# interior_panel.net
KiCad netlist of a schematic drawn in EAGLE
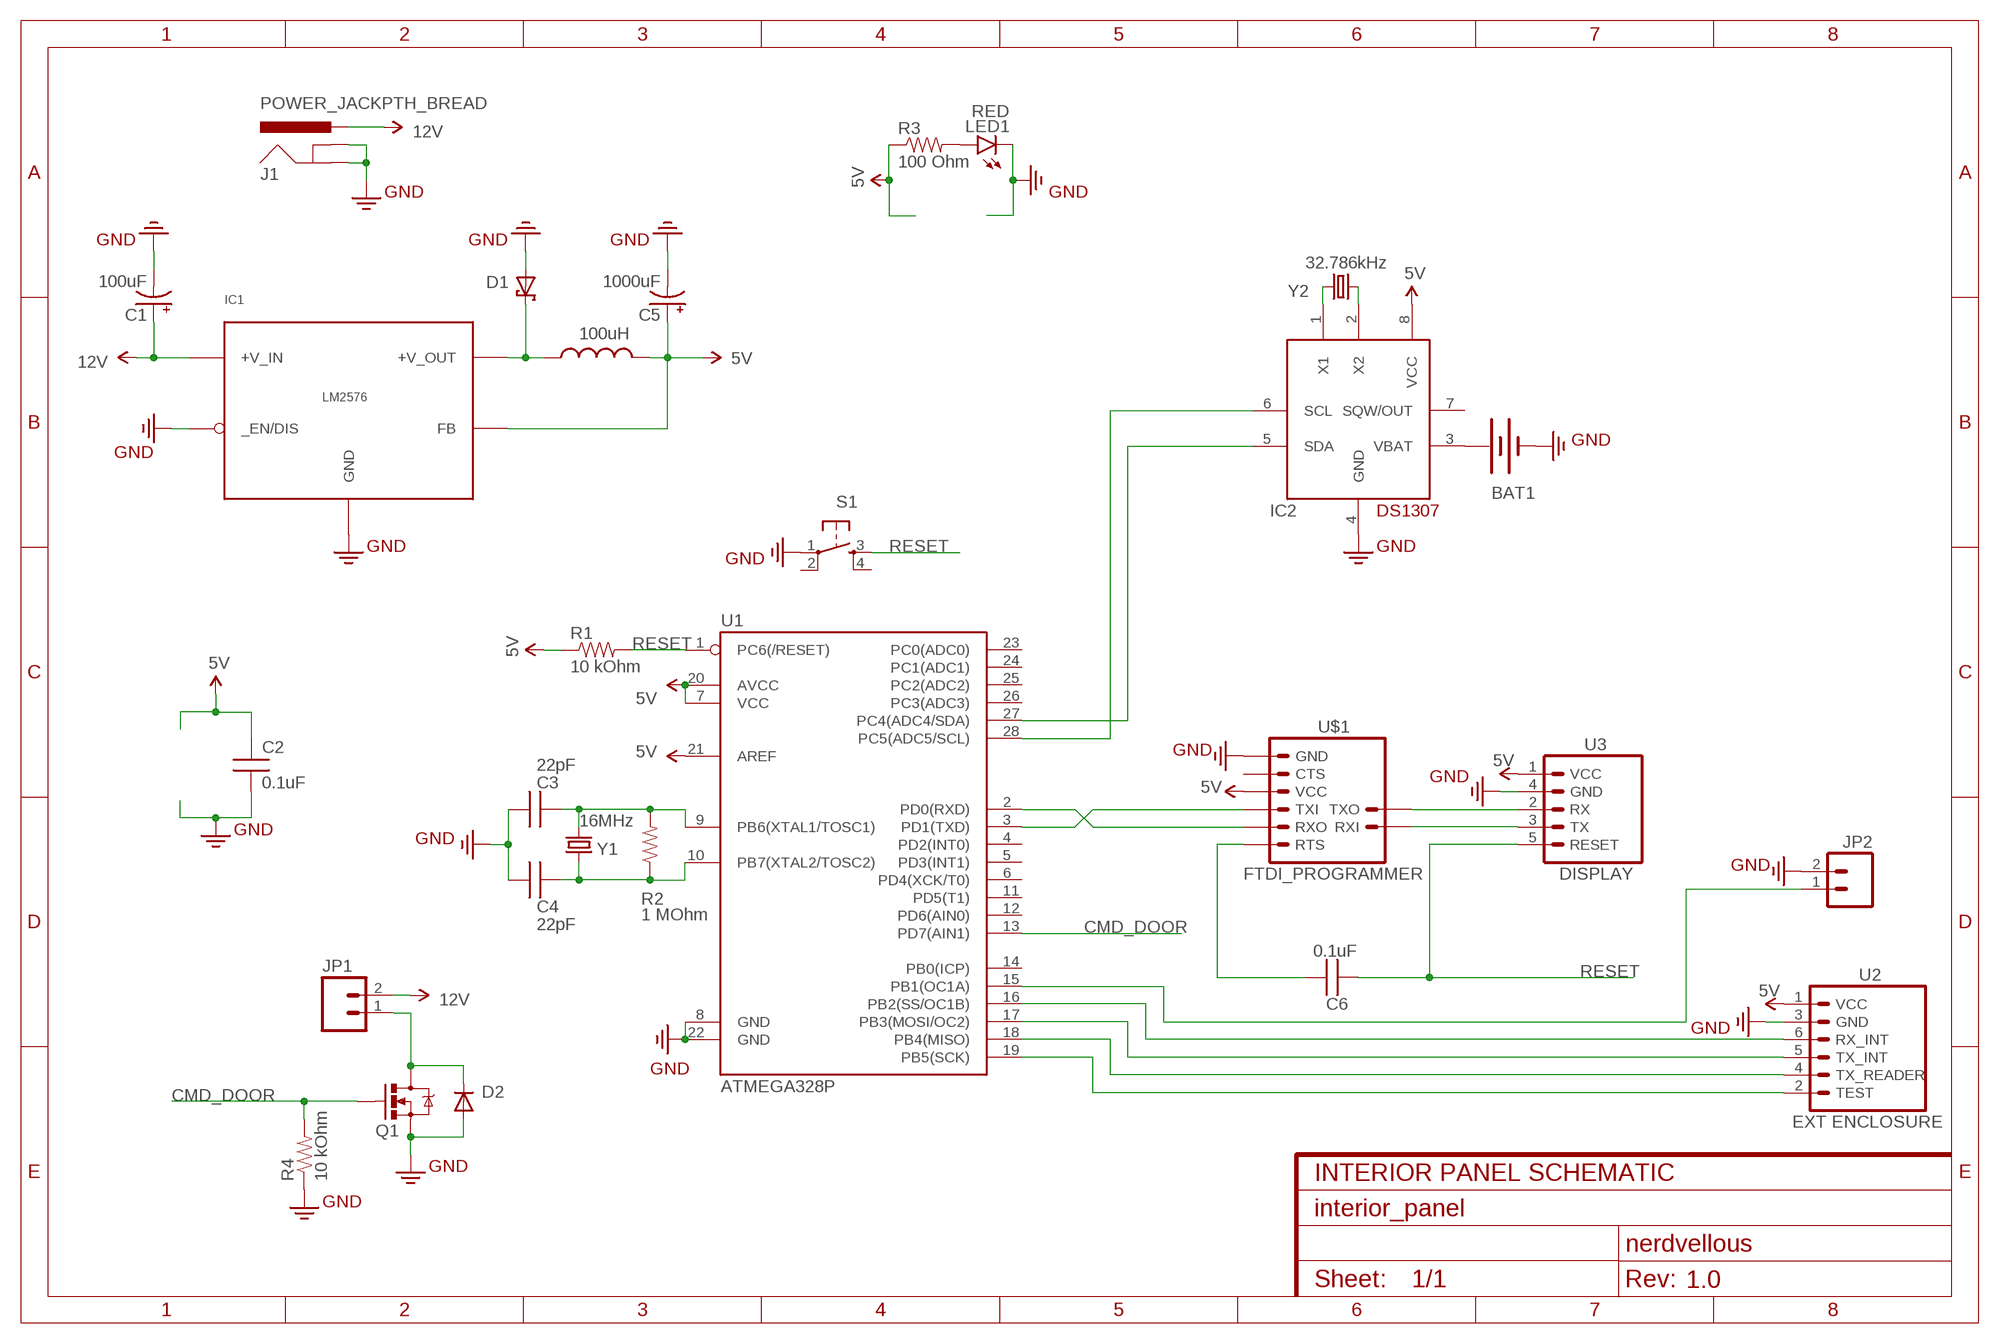
[diagram p0: schematic, sheet 1]

(export (version "E")
  (design (tool "Eeschema 10.0.6"))
  (components
    (comp (ref "BAT1")
      (value "BATTERY12MMFULLPTH")
      (footprint "eagle-import:BATTCON_12MM_FULLPTH")
      (libsource (lib "eagle-import") (part "BATTERY12MMFULLPTH"))
    )
    (comp (ref "C1")
      (value "100uF")
      (footprint "eagle-import:CPOL-RADIAL-100UF-25V")
      (libsource (lib "eagle-import") (part "CAP-100UF"))
    )
    (comp (ref "C2")
      (value "0.1uF")
      (footprint "eagle-import:CAP-PTH-SMALL")
      (libsource (lib "eagle-import") (part "CAP-0.1UF"))
    )
    (comp (ref "C3")
      (value "22pF")
      (footprint "eagle-import:CAP-PTH-SMALL")
      (libsource (lib "eagle-import") (part "CAP-22PF"))
    )
    (comp (ref "C4")
      (value "22pF")
      (footprint "eagle-import:CAP-PTH-SMALL")
      (libsource (lib "eagle-import") (part "CAP-22PF"))
    )
    (comp (ref "C5")
      (value "1000uF")
      (footprint "eagle-import:CPOL-RADIAL-100UF-25V")
      (libsource (lib "eagle-import") (part "CAP-1000UF16V"))
    )
    (comp (ref "C6")
      (value "0.1uF")
      (footprint "eagle-import:CAP-PTH-SMALL")
      (libsource (lib "eagle-import") (part "CAP-0.1UF"))
    )
    (comp (ref "D1")
      (value "1N5822")
      (footprint "eagle-import:DO-201AD")
      (libsource (lib "eagle-import") (part "1N5822"))
    )
    (comp (ref "D2")
      (value "1N4004")
      (footprint "eagle-import:DO-41")
      (libsource (lib "eagle-import") (part "1N4004"))
    )
    (comp (ref "IC1")
      (value "LM2576")
      (footprint "eagle-import:TO-220-5PIN")
      (libsource (lib "eagle-import") (part "LM2576"))
    )
    (comp (ref "IC2")
      (value "DS1307")
      (footprint "eagle-import:DIL08")
      (libsource (lib "eagle-import") (part "DS1307"))
    )
    (comp (ref "J1")
      (value "POWER_JACKPTH_BREAD")
      (footprint "eagle-import:POWER_JACK_PTH_BREAD")
      (libsource (lib "eagle-import") (part "POWER_JACKPTH_BREAD"))
    )
    (comp (ref "JP1")
      (value "M02PTH")
      (footprint "eagle-import:1X02")
      (libsource (lib "eagle-import") (part "M02PTH"))
    )
    (comp (ref "JP2")
      (value "M02PTH")
      (footprint "eagle-import:1X02")
      (libsource (lib "eagle-import") (part "M02PTH"))
    )
    (comp (ref "L1")
      (value "100uH")
      (footprint "eagle-import:RLB0912")
      (libsource (lib "eagle-import") (part "INDUCTORRLB0912"))
    )
    (comp (ref "LED1")
      (value "RED")
      (footprint "eagle-import:LED5MM")
      (libsource (lib "eagle-import") (part "LED5MM"))
    )
    (comp (ref "Q1")
      (value "MOSFET-NCHANNELFQP30N06L")
      (footprint "eagle-import:TO220V")
      (libsource (lib "eagle-import") (part "MOSFET-NCHANNELFQP30N06L"))
    )
    (comp (ref "R1")
      (value "10 kOhm")
      (footprint "eagle-import:AXIAL-0.3")
      (libsource (lib "eagle-import") (part "RES-10KOHM"))
    )
    (comp (ref "R2")
      (value "1 MOhm")
      (footprint "eagle-import:AXIAL-0.3")
      (libsource (lib "eagle-import") (part "RES-1MOHM"))
    )
    (comp (ref "R3")
      (value "100 Ohm")
      (footprint "eagle-import:AXIAL-0.3")
      (libsource (lib "eagle-import") (part "RES-100OHM"))
    )
    (comp (ref "R4")
      (value "10 kOhm")
      (footprint "eagle-import:AXIAL-0.3")
      (libsource (lib "eagle-import") (part "RES-10KOHM"))
    )
    (comp (ref "S1")
      (value "TAC_SWITCHPTH")
      (footprint "eagle-import:TACTILE-PTH")
      (libsource (lib "eagle-import") (part "TAC_SWITCHPTH"))
    )
    (comp (ref "U$1")
      (value "FTDI_PROGRAMMER")
      (footprint "eagle-import:FTDI_CABLE_JUMPER")
      (libsource (lib "eagle-import") (part "FTDI_PROGRAMMER"))
    )
    (comp (ref "U1")
      (value "ATMEGA328P")
      (footprint "eagle-import:DIL28")
      (libsource (lib "eagle-import") (part "ATMEGA328P"))
    )
    (comp (ref "U2")
      (value "EXT ENCLOSURE")
      (footprint "eagle-import:1X06_POL")
      (libsource (lib "eagle-import") (part "CONNECTOR_INT_EXT"))
    )
    (comp (ref "U3")
      (value "DISPLAY")
      (footprint "eagle-import:1X05_POL")
      (libsource (lib "eagle-import") (part "CONNECTOR_DISPLAYPOL"))
    )
    (comp (ref "Y1")
      (value "16MHz")
      (footprint "eagle-import:HC49US")
      (libsource (lib "eagle-import") (part "CRYSTALHC49US"))
    )
    (comp (ref "Y2")
      (value "32.786kHz")
      (footprint "eagle-import:TC26V")
      (libsource (lib "eagle-import") (part "CRYSTALTC26V"))
    )
  )
  (nets
    (net (code "1") (name "/CMD_DOOR") (class "Default")
      (node (ref "Q1") (pin "1") (pinfunction "G_1") (pintype "passive"))
      (node (ref "R4") (pin "P$2") (pinfunction "2_P$2") (pintype "passive"))
      (node (ref "U1") (pin "13") (pinfunction "PD7(AIN1)_13") (pintype "bidirectional"))
    )
    (net (code "2") (name "/RESET") (class "Default")
      (node (ref "C6") (pin "1") (pinfunction "1_1") (pintype "passive"))
      (node (ref "R1") (pin "P$2") (pinfunction "2_P$2") (pintype "passive"))
      (node (ref "S1") (pin "3") (pinfunction "3_3") (pintype "passive"))
      (node (ref "U1") (pin "1") (pinfunction "PC6(/RESET)_1") (pintype "bidirectional"))
      (node (ref "U3") (pin "5") (pinfunction "RESET_5") (pintype "passive"))
    )
    (net (code "3") (name "5V") (class "Default")
      (node (ref "C2") (pin "1") (pinfunction "1_1") (pintype "passive"))
      (node (ref "C5") (pin "1") (pinfunction "+_1") (pintype "passive"))
      (node (ref "IC1") (pin "P$4") (pinfunction "FB_P$4") (pintype "input"))
      (node (ref "IC2") (pin "8") (pinfunction "VCC_8") (pintype "bidirectional"))
      (node (ref "L1") (pin "2") (pinfunction "2_2") (pintype "passive"))
      (node (ref "R1") (pin "P$1") (pinfunction "1_P$1") (pintype "passive"))
      (node (ref "R3") (pin "P$1") (pinfunction "1_P$1") (pintype "passive"))
      (node (ref "U$1") (pin "VCC") (pinfunction "VCC_VCC") (pintype "passive"))
      (node (ref "U1") (pin "20") (pinfunction "AVCC_20") (pintype "bidirectional"))
      (node (ref "U1") (pin "21") (pinfunction "AREF_21") (pintype "bidirectional"))
      (node (ref "U1") (pin "7") (pinfunction "VCC_7") (pintype "bidirectional"))
      (node (ref "U2") (pin "1") (pinfunction "VCC_1") (pintype "passive"))
      (node (ref "U3") (pin "1") (pinfunction "VCC_1") (pintype "passive"))
    )
    (net (code "4") (name "12V") (class "Default")
      (node (ref "C1") (pin "1") (pinfunction "+_1") (pintype "passive"))
      (node (ref "IC1") (pin "P$1") (pinfunction "+V_IN_P$1") (pintype "input"))
      (node (ref "J1") (pin "PWR") (pinfunction "PWR_PWR") (pintype "bidirectional"))
      (node (ref "JP1") (pin "2") (pinfunction "2_2") (pintype "passive"))
    )
    (net (code "5") (name "GND") (class "Default")
      (node (ref "BAT1") (pin "-") (pinfunction "-_-") (pintype "bidirectional"))
      (node (ref "C1") (pin "2") (pinfunction "-_2") (pintype "passive"))
      (node (ref "C2") (pin "2") (pinfunction "2_2") (pintype "passive"))
      (node (ref "C3") (pin "2") (pinfunction "2_2") (pintype "passive"))
      (node (ref "C4") (pin "2") (pinfunction "2_2") (pintype "passive"))
      (node (ref "C5") (pin "2") (pinfunction "-_2") (pintype "passive"))
      (node (ref "D1") (pin "A") (pinfunction "A_A") (pintype "passive"))
      (node (ref "D2") (pin "A") (pinfunction "A_A") (pintype "passive"))
      (node (ref "IC1") (pin "P$3") (pinfunction "GND_P$3") (pintype "power_in"))
      (node (ref "IC1") (pin "P$5") (pinfunction "_EN/DIS_P$5") (pintype "input"))
      (node (ref "IC2") (pin "4") (pinfunction "GND_4") (pintype "power_in"))
      (node (ref "J1") (pin "GND") (pinfunction "GND_GND") (pintype "bidirectional"))
      (node (ref "J1") (pin "GNDBREAK") (pinfunction "GNDBREAK_GNDBREAK") (pintype "bidirectional"))
      (node (ref "JP2") (pin "2") (pinfunction "2_2") (pintype "passive"))
      (node (ref "LED1") (pin "K") (pinfunction "C_K") (pintype "passive"))
      (node (ref "Q1") (pin "3") (pinfunction "S_3") (pintype "passive"))
      (node (ref "R4") (pin "P$1") (pinfunction "1_P$1") (pintype "passive"))
      (node (ref "S1") (pin "1") (pinfunction "1_1") (pintype "passive"))
      (node (ref "U$1") (pin "GND") (pinfunction "GND_GND") (pintype "passive"))
      (node (ref "U1") (pin "22") (pinfunction "GND_22") (pintype "bidirectional"))
      (node (ref "U1") (pin "8") (pinfunction "GND_8") (pintype "bidirectional"))
      (node (ref "U2") (pin "3") (pinfunction "GND_3") (pintype "passive"))
      (node (ref "U3") (pin "4") (pinfunction "GND_4") (pintype "passive"))
    )
    (net (code "6") (name "Net-(C6-Pad2)") (class "Default")
      (node (ref "C6") (pin "2") (pinfunction "2_2") (pintype "passive"))
      (node (ref "U$1") (pin "RTS") (pinfunction "RTS_RTS") (pintype "passive"))
    )
    (net (code "7") (name "Net-(IC1-+V_OUT)") (class "Default")
      (node (ref "D1") (pin "C") (pinfunction "C_C") (pintype "passive"))
      (node (ref "IC1") (pin "P$2") (pinfunction "+V_OUT_P$2") (pintype "output"))
      (node (ref "L1") (pin "1") (pinfunction "1_1") (pintype "passive"))
    )
    (net (code "8") (name "Net-(IC2-SCL)") (class "Default")
      (node (ref "IC2") (pin "6") (pinfunction "SCL_6") (pintype "bidirectional"))
      (node (ref "U1") (pin "28") (pinfunction "PC5(ADC5/SCL)_28") (pintype "bidirectional"))
    )
    (net (code "9") (name "Net-(IC2-SDA)") (class "Default")
      (node (ref "IC2") (pin "5") (pinfunction "SDA_5") (pintype "bidirectional"))
      (node (ref "U1") (pin "27") (pinfunction "PC4(ADC4/SDA)_27") (pintype "bidirectional"))
    )
    (net (code "10") (name "Net-(IC2-VBAT)") (class "Default")
      (node (ref "BAT1") (pin "+1") (pinfunction "+_+1") (pintype "bidirectional"))
      (node (ref "BAT1") (pin "+2") (pinfunction "+_+2") (pintype "bidirectional"))
      (node (ref "IC2") (pin "3") (pinfunction "VBAT_3") (pintype "bidirectional"))
    )
    (net (code "11") (name "Net-(IC2-X1)") (class "Default")
      (node (ref "IC2") (pin "1") (pinfunction "X1_1") (pintype "passive"))
      (node (ref "Y2") (pin "1") (pinfunction "1_1") (pintype "passive"))
    )
    (net (code "12") (name "Net-(IC2-X2)") (class "Default")
      (node (ref "IC2") (pin "2") (pinfunction "X2_2") (pintype "passive"))
      (node (ref "Y2") (pin "2") (pinfunction "2_2") (pintype "passive"))
    )
    (net (code "13") (name "Net-(Q1-D)") (class "Default")
      (node (ref "D2") (pin "C") (pinfunction "C_C") (pintype "passive"))
      (node (ref "JP1") (pin "1") (pinfunction "1_1") (pintype "passive"))
      (node (ref "Q1") (pin "2") (pinfunction "D_2") (pintype "passive"))
    )
    (net (code "14") (name "Net-(R2-1)") (class "Default")
      (node (ref "C4") (pin "1") (pinfunction "1_1") (pintype "passive"))
      (node (ref "R2") (pin "P$1") (pinfunction "1_P$1") (pintype "passive"))
      (node (ref "U1") (pin "10") (pinfunction "PB7(XTAL2/TOSC2)_10") (pintype "bidirectional"))
      (node (ref "Y1") (pin "1") (pinfunction "1_1") (pintype "passive"))
    )
    (net (code "15") (name "Net-(R2-2)") (class "Default")
      (node (ref "C3") (pin "1") (pinfunction "1_1") (pintype "passive"))
      (node (ref "R2") (pin "P$2") (pinfunction "2_P$2") (pintype "passive"))
      (node (ref "U1") (pin "9") (pinfunction "PB6(XTAL1/TOSC1)_9") (pintype "bidirectional"))
      (node (ref "Y1") (pin "2") (pinfunction "2_2") (pintype "passive"))
    )
    (net (code "16") (name "Net-(R3-2)") (class "Default")
      (node (ref "LED1") (pin "A") (pinfunction "A_A") (pintype "passive"))
      (node (ref "R3") (pin "P$2") (pinfunction "2_P$2") (pintype "passive"))
    )
    (net (code "17") (name "Net-(U$1-RXI)") (class "Default")
      (node (ref "U$1") (pin "RXIC") (pinfunction "RXI_RXIC") (pintype "bidirectional"))
      (node (ref "U3") (pin "3") (pinfunction "TX_3") (pintype "passive"))
    )
    (net (code "18") (name "Net-(U$1-RXO)") (class "Default")
      (node (ref "U$1") (pin "TXFTDI") (pinfunction "RXO_TXFTDI") (pintype "passive"))
      (node (ref "U1") (pin "2") (pinfunction "PD0(RXD)_2") (pintype "bidirectional"))
    )
    (net (code "19") (name "Net-(U$1-TXI)") (class "Default")
      (node (ref "U$1") (pin "RXFTDI") (pinfunction "TXI_RXFTDI") (pintype "passive"))
      (node (ref "U1") (pin "3") (pinfunction "PD1(TXD)_3") (pintype "bidirectional"))
    )
    (net (code "20") (name "Net-(U$1-TXO)") (class "Default")
      (node (ref "U$1") (pin "TXIC") (pinfunction "TXO_TXIC") (pintype "bidirectional"))
      (node (ref "U3") (pin "2") (pinfunction "RX_2") (pintype "passive"))
    )
    (net (code "21") (name "Net-(U1-PB1(OC1A))") (class "Default")
      (node (ref "JP2") (pin "1") (pinfunction "1_1") (pintype "passive"))
      (node (ref "U1") (pin "15") (pinfunction "PB1(OC1A)_15") (pintype "bidirectional"))
    )
    (net (code "22") (name "Net-(U1-PB2(SS{slash}OC1B))") (class "Default")
      (node (ref "U1") (pin "16") (pinfunction "PB2(SS/OC1B)_16") (pintype "bidirectional"))
      (node (ref "U2") (pin "6") (pinfunction "RX_INT_6") (pintype "passive"))
    )
    (net (code "23") (name "Net-(U1-PB3(MOSI{slash}OC2))") (class "Default")
      (node (ref "U1") (pin "17") (pinfunction "PB3(MOSI/OC2)_17") (pintype "bidirectional"))
      (node (ref "U2") (pin "5") (pinfunction "TX_INT_5") (pintype "passive"))
    )
    (net (code "24") (name "Net-(U1-PB4(MISO))") (class "Default")
      (node (ref "U1") (pin "18") (pinfunction "PB4(MISO)_18") (pintype "bidirectional"))
      (node (ref "U2") (pin "4") (pinfunction "TX_READER_4") (pintype "passive"))
    )
    (net (code "25") (name "Net-(U1-PB5(SCK))") (class "Default")
      (node (ref "U1") (pin "19") (pinfunction "PB5(SCK)_19") (pintype "bidirectional"))
      (node (ref "U2") (pin "2") (pinfunction "TEST_2") (pintype "passive"))
    )
    (net (code "26") (name "unconnected-(IC2-SQW{slash}OUT-Pad7)") (class "Default")
      (node (ref "IC2") (pin "7") (pinfunction "SQW/OUT_7") (pintype "bidirectional"))
    )
    (net (code "27") (name "unconnected-(S1-Pad2)") (class "Default")
      (node (ref "S1") (pin "2") (pinfunction "2_2") (pintype "passive"))
    )
    (net (code "28") (name "unconnected-(S1-Pad4)") (class "Default")
      (node (ref "S1") (pin "4") (pinfunction "4_4") (pintype "passive"))
    )
    (net (code "29") (name "unconnected-(U$1-PadCTS)") (class "Default")
      (node (ref "U$1") (pin "CTS") (pinfunction "CTS_CTS") (pintype "passive"))
    )
    (net (code "30") (name "unconnected-(U1-PB0(ICP)-Pad14)") (class "Default")
      (node (ref "U1") (pin "14") (pinfunction "PB0(ICP)_14") (pintype "bidirectional"))
    )
    (net (code "31") (name "unconnected-(U1-PC0(ADC0)-Pad23)") (class "Default")
      (node (ref "U1") (pin "23") (pinfunction "PC0(ADC0)_23") (pintype "bidirectional"))
    )
    (net (code "32") (name "unconnected-(U1-PC1(ADC1)-Pad24)") (class "Default")
      (node (ref "U1") (pin "24") (pinfunction "PC1(ADC1)_24") (pintype "bidirectional"))
    )
    (net (code "33") (name "unconnected-(U1-PC2(ADC2)-Pad25)") (class "Default")
      (node (ref "U1") (pin "25") (pinfunction "PC2(ADC2)_25") (pintype "bidirectional"))
    )
    (net (code "34") (name "unconnected-(U1-PC3(ADC3)-Pad26)") (class "Default")
      (node (ref "U1") (pin "26") (pinfunction "PC3(ADC3)_26") (pintype "bidirectional"))
    )
    (net (code "35") (name "unconnected-(U1-PD2(INT0)-Pad4)") (class "Default")
      (node (ref "U1") (pin "4") (pinfunction "PD2(INT0)_4") (pintype "bidirectional"))
    )
    (net (code "36") (name "unconnected-(U1-PD3(INT1)-Pad5)") (class "Default")
      (node (ref "U1") (pin "5") (pinfunction "PD3(INT1)_5") (pintype "bidirectional"))
    )
    (net (code "37") (name "unconnected-(U1-PD4(XCK{slash}T0)-Pad6)") (class "Default")
      (node (ref "U1") (pin "6") (pinfunction "PD4(XCK/T0)_6") (pintype "bidirectional"))
    )
    (net (code "38") (name "unconnected-(U1-PD5(T1)-Pad11)") (class "Default")
      (node (ref "U1") (pin "11") (pinfunction "PD5(T1)_11") (pintype "bidirectional"))
    )
    (net (code "39") (name "unconnected-(U1-PD6(AIN0)-Pad12)") (class "Default")
      (node (ref "U1") (pin "12") (pinfunction "PD6(AIN0)_12") (pintype "bidirectional"))
    )
  )
)
